# Power_Supplies.net
KiCad netlist of a schematic drawn in Altium Designer
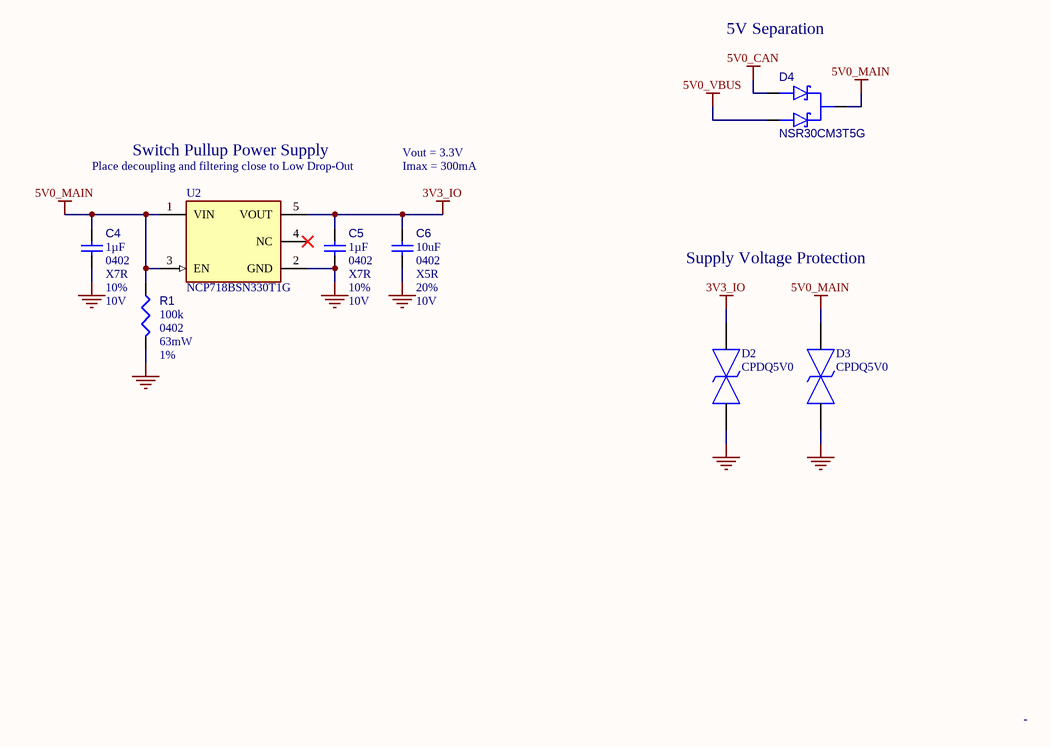
[diagram p0: Power Supplies.SchDoc]

(export (version "E")
  (design (tool "Eeschema 10.0.6"))
  (components
    (comp (ref "C4")
      (value "1µF")
      (footprint "CAPC1005X55X30NL05T10")
      (fields
        (field (name "CASE/PACKAGE") "0402")
        (field (name "VOLTAGE RATING") "10V")
        (field (name "CAPACITOR TYPE") "X7R")
        (field (name "TOLERANCE") "10%")
        (field (name "Comment") "GRM155Z71A105KE01D")
      )
      (libsource (lib "Personal Workspace") (part "CAP-NP-2"))
    )
    (comp (ref "C5")
      (value "1µF")
      (footprint "CAPC1005X55X30NL05T10")
      (fields
        (field (name "CASE/PACKAGE") "0402")
        (field (name "VOLTAGE RATING") "10V")
        (field (name "CAPACITOR TYPE") "X7R")
        (field (name "TOLERANCE") "10%")
        (field (name "Comment") "GRM155Z71A105KE01D")
      )
      (libsource (lib "Personal Workspace") (part "CAP-NP-2"))
    )
    (comp (ref "C6")
      (value "10uF")
      (footprint "CAPC1005X55X30NL05T10")
      (fields
        (field (name "CAPACITOR TYPE") "X5R")
        (field (name "VOLTAGE RATING") "10V")
        (field (name "TOLERANCE") "20%")
        (field (name "CASE/PACKAGE") "0402")
        (field (name "Comment") "GRM155R61A106ME11J")
      )
      (libsource (lib "Personal Workspace") (part "CAP-NP-2"))
    )
    (comp (ref "D2")
      (value "CPDQ5V0")
      (footprint "MBTB-D-SOD-923F-IMP-0402")
      (description "18.6V Clamp 9.4A (8/20Âµs) Ipp Tvs Diode Surface Mount 0402/SOD-923F")
      (fields (field (name "MF") "Comchip Technology") (field (name "MP") "CPDQ5V0-HF"))
      (libsource (lib "Personal Workspace") (part "CPDQ5V0-HF"))
    )
    (comp (ref "D3")
      (value "CPDQ5V0")
      (footprint "MBTB-D-SOD-923F-IMP-0402")
      (description "18.6V Clamp 9.4A (8/20Âµs) Ipp Tvs Diode Surface Mount 0402/SOD-923F")
      (fields (field (name "MF") "Comchip Technology") (field (name "MP") "CPDQ5V0-HF"))
      (libsource (lib "Personal Workspace") (part "CPDQ5V0-HF"))
    )
    (comp (ref "D4")
      (value "NSR30CM3T5G")
      (footprint "ONSC-SOT-723-3-631AA-01_C_V")
      (description "Dual Common Cathode Schottky Barrier Diodes, 3-Pin SOT-723, Pb-Free, Tape and Reel")
      (libsource (lib "Personal Workspace") (part "D-SKY-AAK-3"))
    )
    (comp (ref "R1")
      (value "100k")
      (footprint "RESC0402(1005)_L")
      (description "100K 0.063W 1% 0402 (1005 Metric)  SMD")
      (fields
        (field (name "POWER") "63mW")
        (field (name "CASE/PACKAGE") "0402")
        (field (name "TOLERANCE") "1%")
        (field (name "Comment") "100KR2F")
      )
      (libsource (lib "Personal Workspace") (part "100KR2F"))
    )
    (comp (ref "U2")
      (value "NCP718BSN330T1G")
      (footprint "SOT95P280X100-5N")
      (description "Fixed Positive LDO Regulator, 3.3V, 440V Dropout, PDSO5")
      (libsource (lib "Personal Workspace") (part "96048095611b4a9579e1e315950d302"))
    )
  )
  (nets
    (net (code "1") (name "3V3_IO") (class "Default")
      (node (ref "C5") (pin "1") (pinfunction "1_1") (pintype "passive"))
      (node (ref "C6") (pin "1") (pinfunction "1_1") (pintype "passive"))
      (node (ref "D2") (pin "1") (pinfunction "K_1") (pintype "passive"))
      (node (ref "U2") (pin "5") (pinfunction "VOUT_5") (pintype "power_in"))
    )
    (net (code "2") (name "5V0_CAN") (class "Default")
      (node (ref "D4") (pin "1") (pinfunction "A1_1") (pintype "passive"))
    )
    (net (code "3") (name "5V0_MAIN") (class "Default")
      (node (ref "C4") (pin "1") (pinfunction "1_1") (pintype "passive"))
      (node (ref "D3") (pin "1") (pinfunction "K_1") (pintype "passive"))
      (node (ref "D4") (pin "3") (pinfunction "K_3") (pintype "passive"))
      (node (ref "R1") (pin "1") (pinfunction "1_1") (pintype "passive"))
      (node (ref "U2") (pin "1") (pinfunction "VIN_1") (pintype "power_in"))
      (node (ref "U2") (pin "3") (pinfunction "EN_3") (pintype "input"))
    )
    (net (code "4") (name "5V0_VBUS") (class "Default")
      (node (ref "D4") (pin "2") (pinfunction "A2_2") (pintype "passive"))
    )
    (net (code "5") (name "GND") (class "Default")
      (node (ref "C4") (pin "2") (pinfunction "2_2") (pintype "passive"))
      (node (ref "C5") (pin "2") (pinfunction "2_2") (pintype "passive"))
      (node (ref "C6") (pin "2") (pinfunction "2_2") (pintype "passive"))
      (node (ref "D2") (pin "2") (pinfunction "A_2") (pintype "passive"))
      (node (ref "D3") (pin "2") (pinfunction "A_2") (pintype "passive"))
      (node (ref "R1") (pin "2") (pinfunction "2_2") (pintype "passive"))
      (node (ref "U2") (pin "2") (pinfunction "GND_2") (pintype "power_in"))
    )
    (net (code "6") (name "unconnected-(U2-NC-Pad4)") (class "Default")
      (node (ref "U2") (pin "4") (pinfunction "NC_4") (pintype "passive+no_connect"))
    )
  )
)
